# Radio_Unit.net
KiCad netlist of a schematic drawn in Altium Designer
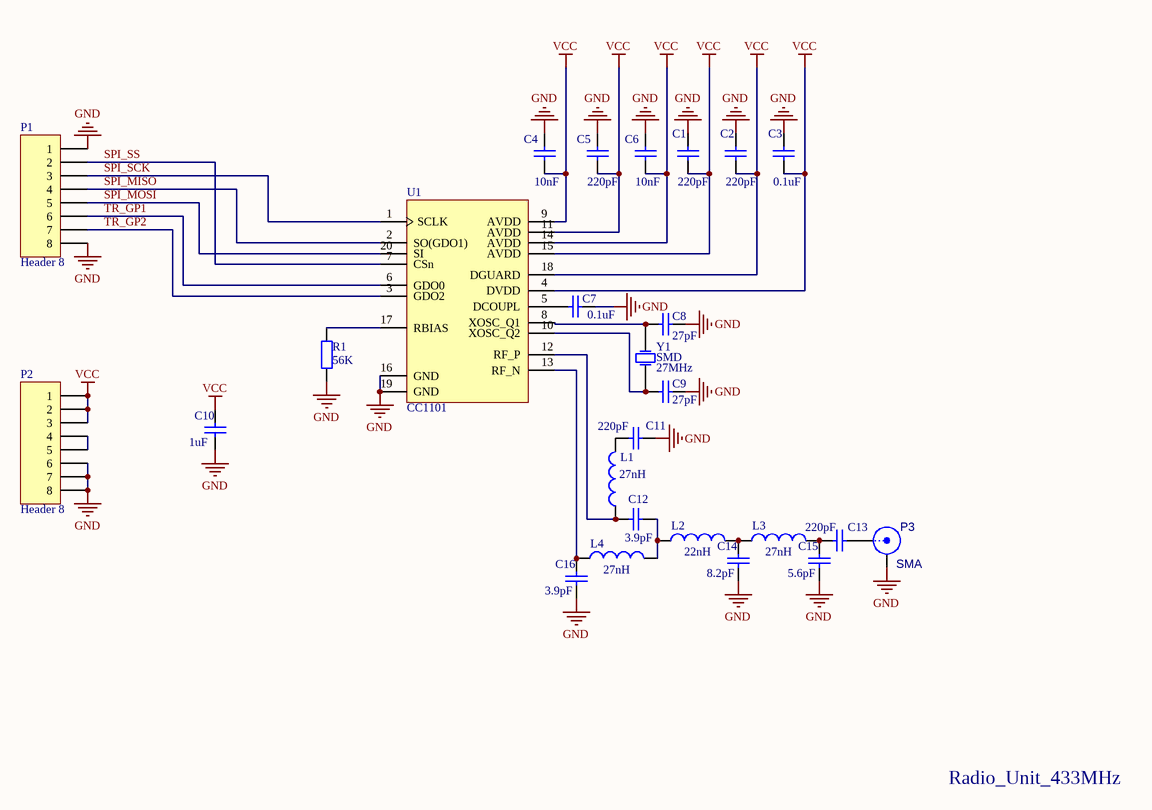
[diagram p0: Radio_Unit.SchDoc]

(export (version "E")
  (design (tool "Eeschema 10.0.6"))
  (components
    (comp (ref "C1")
      (value "220pF")
      (footprint "C0603")
      (description "Capasitor_SMD_0808/")
      (fields (field (name "Comment") "0805"))
      (libsource (lib "NEW") (part "Capasitor_SMD_0805"))
    )
    (comp (ref "C2")
      (value "220pF")
      (footprint "C0603")
      (description "Capasitor_SMD_0808/")
      (fields (field (name "Comment") "0805"))
      (libsource (lib "NEW") (part "Capasitor_SMD_0805"))
    )
    (comp (ref "C3")
      (value "0.1uF")
      (footprint "C0603")
      (description "Capasitor_SMD_0808/")
      (fields (field (name "Comment") "0805"))
      (libsource (lib "NEW") (part "Capasitor_SMD_0805"))
    )
    (comp (ref "C4")
      (value "10nF")
      (footprint "C0603")
      (description "Capasitor_SMD_0808/")
      (fields (field (name "Comment") "0805"))
      (libsource (lib "NEW") (part "Capasitor_SMD_0805"))
    )
    (comp (ref "C5")
      (value "220pF")
      (footprint "C0603")
      (description "Capasitor_SMD_0808/")
      (fields (field (name "Comment") "0805"))
      (libsource (lib "NEW") (part "Capasitor_SMD_0805"))
    )
    (comp (ref "C6")
      (value "10nF")
      (footprint "C0603")
      (description "Capasitor_SMD_0808/")
      (fields (field (name "Comment") "0805"))
      (libsource (lib "NEW") (part "Capasitor_SMD_0805"))
    )
    (comp (ref "C7")
      (value "0.1uF")
      (footprint "C0603")
      (description "Capasitor_SMD_0808/")
      (fields (field (name "Comment") "0805"))
      (libsource (lib "NEW") (part "Capasitor_SMD_0805"))
    )
    (comp (ref "C8")
      (value "27pF")
      (footprint "C0603")
      (description "Capasitor_SMD_0808/")
      (fields (field (name "Comment") "0805"))
      (libsource (lib "NEW") (part "Capasitor_SMD_0805"))
    )
    (comp (ref "C9")
      (value "27pF")
      (footprint "C0603")
      (description "Capasitor_SMD_0808/")
      (fields (field (name "Comment") "0805"))
      (libsource (lib "NEW") (part "Capasitor_SMD_0805"))
    )
    (comp (ref "C10")
      (value "1uF")
      (footprint "C0603")
      (description "Capasitor_SMD_0808/")
      (fields (field (name "Comment") "0805"))
      (libsource (lib "NEW") (part "Capasitor_SMD_0805"))
    )
    (comp (ref "C11")
      (value "220pF")
      (footprint "C0603")
      (description "Capasitor_SMD_0808/")
      (fields (field (name "Comment") "0805"))
      (libsource (lib "NEW") (part "Capasitor_SMD_0805"))
    )
    (comp (ref "C12")
      (value "3.9pF")
      (footprint "C0603")
      (description "Capasitor_SMD_0808/")
      (fields (field (name "Comment") "0805"))
      (libsource (lib "NEW") (part "Capasitor_SMD_0805"))
    )
    (comp (ref "C13")
      (value "220pF")
      (footprint "C0603")
      (description "Capasitor_SMD_0808/")
      (fields (field (name "Comment") "0805"))
      (libsource (lib "NEW") (part "Capasitor_SMD_0805"))
    )
    (comp (ref "C14")
      (value "8.2pF")
      (footprint "C0603")
      (description "Capasitor_SMD_0808/")
      (fields (field (name "Comment") "0805"))
      (libsource (lib "NEW") (part "Capasitor_SMD_0805"))
    )
    (comp (ref "C15")
      (value "5.6pF")
      (footprint "C0603")
      (description "Capasitor_SMD_0808/")
      (fields (field (name "Comment") "0805"))
      (libsource (lib "NEW") (part "Capasitor_SMD_0805"))
    )
    (comp (ref "C16")
      (value "3.9pF")
      (footprint "C0603")
      (description "Capasitor_SMD_0808/")
      (fields (field (name "Comment") "0805"))
      (libsource (lib "NEW") (part "Capasitor_SMD_0805"))
    )
    (comp (ref "L1")
      (value "27nH")
      (footprint "L0603")
      (fields (field (name "Comment") "SMD"))
      (libsource (lib "NEW") (part "Induktor_SMD"))
    )
    (comp (ref "L2")
      (value "22nH")
      (footprint "L0603")
      (fields (field (name "Comment") "SMD"))
      (libsource (lib "NEW") (part "Induktor_SMD"))
    )
    (comp (ref "L3")
      (value "27nH")
      (footprint "L0603")
      (fields (field (name "Comment") "SMD"))
      (libsource (lib "NEW") (part "Induktor_SMD"))
    )
    (comp (ref "L4")
      (value "27nH")
      (footprint "L0603")
      (fields (field (name "Comment") "SMD"))
      (libsource (lib "NEW") (part "Induktor_SMD"))
    )
    (comp (ref "P1")
      (value "Header 8")
      (footprint "HDR1X8")
      (description "Header, 8-Pin")
      (fields (field (name "PUBLISHER") "Altium Limited"))
      (libsource (lib "Miscellaneous Connectors") (part "Header 8"))
    )
    (comp (ref "P2")
      (value "Header 8")
      (footprint "HDR1X8")
      (description "Header, 8-Pin")
      (fields (field (name "PUBLISHER") "Altium Limited"))
      (libsource (lib "Miscellaneous Connectors") (part "Header 8"))
    )
    (comp (ref "P3")
      (value "SMA")
      (footprint "SMA")
      (fields (field (name "PUBLISHER") "Altium Limited"))
      (libsource (lib "NEW") (part "SMA"))
    )
    (comp (ref "R1")
      (value "56K")
      (footprint "C0603")
      (description "Resistor")
      (fields (field (name "Comment") "RES"))
      (libsource (lib "NEW") (part "RES"))
    )
    (comp (ref "U1") (value "CC1101") (footprint "VQFN20") (libsource (lib "NEW") (part "CC1101")))
    (comp (ref "Y1")
      (value "SMD")
      (footprint "Quartz_SMD0603")
      (fields (field (name "ALTIUM_UNNAMED_1") "27MHz"))
      (libsource (lib "NEW") (part "Quartz_SMD"))
    )
  )
  (nets
    (net (code "1") (name "/SPI_MISO") (class "Default")
      (node (ref "P1") (pin "4") (pinfunction "4_4") (pintype "passive"))
      (node (ref "U1") (pin "2") (pinfunction "SO(GDO1)_2") (pintype "passive"))
    )
    (net (code "2") (name "/SPI_MOSI") (class "Default")
      (node (ref "P1") (pin "5") (pinfunction "5_5") (pintype "passive"))
      (node (ref "U1") (pin "20") (pinfunction "SI_20") (pintype "passive"))
    )
    (net (code "3") (name "/SPI_SCK") (class "Default")
      (node (ref "P1") (pin "3") (pinfunction "3_3") (pintype "passive"))
      (node (ref "U1") (pin "1") (pinfunction "SCLK_1") (pintype "passive"))
    )
    (net (code "4") (name "/SPI_SS") (class "Default")
      (node (ref "P1") (pin "2") (pinfunction "2_2") (pintype "passive"))
      (node (ref "U1") (pin "7") (pinfunction "CSn_7") (pintype "passive"))
    )
    (net (code "5") (name "/TR_GP1") (class "Default")
      (node (ref "P1") (pin "6") (pinfunction "6_6") (pintype "passive"))
      (node (ref "U1") (pin "6") (pinfunction "GDO0_6") (pintype "passive"))
    )
    (net (code "6") (name "/TR_GP2") (class "Default")
      (node (ref "P1") (pin "7") (pinfunction "7_7") (pintype "passive"))
      (node (ref "U1") (pin "3") (pinfunction "GDO2_3") (pintype "passive"))
    )
    (net (code "7") (name "GND") (class "Default")
      (node (ref "C1") (pin "1") (pinfunction "1_1") (pintype "passive"))
      (node (ref "C10") (pin "2") (pinfunction "2_2") (pintype "passive"))
      (node (ref "C11") (pin "2") (pinfunction "2_2") (pintype "passive"))
      (node (ref "C14") (pin "1") (pinfunction "1_1") (pintype "passive"))
      (node (ref "C15") (pin "1") (pinfunction "1_1") (pintype "passive"))
      (node (ref "C16") (pin "1") (pinfunction "1_1") (pintype "passive"))
      (node (ref "C2") (pin "1") (pinfunction "1_1") (pintype "passive"))
      (node (ref "C3") (pin "1") (pinfunction "1_1") (pintype "passive"))
      (node (ref "C4") (pin "1") (pinfunction "1_1") (pintype "passive"))
      (node (ref "C5") (pin "1") (pinfunction "1_1") (pintype "passive"))
      (node (ref "C6") (pin "1") (pinfunction "1_1") (pintype "passive"))
      (node (ref "C7") (pin "2") (pinfunction "2_2") (pintype "passive"))
      (node (ref "C8") (pin "2") (pinfunction "2_2") (pintype "passive"))
      (node (ref "C9") (pin "2") (pinfunction "2_2") (pintype "passive"))
      (node (ref "P1") (pin "1") (pinfunction "1_1") (pintype "passive"))
      (node (ref "P1") (pin "8") (pinfunction "8_8") (pintype "passive"))
      (node (ref "P2") (pin "6") (pinfunction "6_6") (pintype "passive"))
      (node (ref "P2") (pin "7") (pinfunction "7_7") (pintype "passive"))
      (node (ref "P2") (pin "8") (pinfunction "8_8") (pintype "passive"))
      (node (ref "P3") (pin "2") (pinfunction "Y_2") (pintype "passive"))
      (node (ref "R1") (pin "1") (pinfunction "1_1") (pintype "passive"))
      (node (ref "U1") (pin "16") (pinfunction "GND_16") (pintype "passive"))
      (node (ref "U1") (pin "19") (pinfunction "GND_19") (pintype "passive"))
    )
    (net (code "8") (name "Net-(C11-Pad1)") (class "Default")
      (node (ref "C11") (pin "1") (pinfunction "1_1") (pintype "passive"))
      (node (ref "L1") (pin "2") (pinfunction "2_2") (pintype "passive"))
    )
    (net (code "9") (name "Net-(C12-Pad1)") (class "Default")
      (node (ref "C12") (pin "1") (pinfunction "1_1") (pintype "passive"))
      (node (ref "L2") (pin "1") (pinfunction "1_1") (pintype "passive"))
      (node (ref "L4") (pin "2") (pinfunction "2_2") (pintype "passive"))
    )
    (net (code "10") (name "Net-(C13-Pad1)") (class "Default")
      (node (ref "C13") (pin "1") (pinfunction "1_1") (pintype "passive"))
      (node (ref "C15") (pin "2") (pinfunction "2_2") (pintype "passive"))
      (node (ref "L3") (pin "2") (pinfunction "2_2") (pintype "passive"))
    )
    (net (code "11") (name "Net-(C14-Pad2)") (class "Default")
      (node (ref "C14") (pin "2") (pinfunction "2_2") (pintype "passive"))
      (node (ref "L2") (pin "2") (pinfunction "2_2") (pintype "passive"))
      (node (ref "L3") (pin "1") (pinfunction "1_1") (pintype "passive"))
    )
    (net (code "12") (name "Net-(P2-Pad4)") (class "Default")
      (node (ref "P2") (pin "4") (pinfunction "4_4") (pintype "passive"))
      (node (ref "P2") (pin "5") (pinfunction "5_5") (pintype "passive"))
    )
    (net (code "13") (name "Net-(P3-X)") (class "Default")
      (node (ref "C13") (pin "2") (pinfunction "2_2") (pintype "passive"))
      (node (ref "P3") (pin "1") (pinfunction "X_1") (pintype "passive"))
    )
    (net (code "14") (name "Net-(U1-DCOUPL)") (class "Default")
      (node (ref "C7") (pin "1") (pinfunction "1_1") (pintype "passive"))
      (node (ref "U1") (pin "5") (pinfunction "DCOUPL_5") (pintype "passive"))
    )
    (net (code "15") (name "Net-(U1-RBIAS)") (class "Default")
      (node (ref "R1") (pin "2") (pinfunction "2_2") (pintype "passive"))
      (node (ref "U1") (pin "17") (pinfunction "RBIAS_17") (pintype "passive"))
    )
    (net (code "16") (name "Net-(U1-RF_N)") (class "Default")
      (node (ref "C16") (pin "2") (pinfunction "2_2") (pintype "passive"))
      (node (ref "L4") (pin "1") (pinfunction "1_1") (pintype "passive"))
      (node (ref "U1") (pin "13") (pinfunction "RF_N_13") (pintype "passive"))
    )
    (net (code "17") (name "Net-(U1-RF_P)") (class "Default")
      (node (ref "C12") (pin "2") (pinfunction "2_2") (pintype "passive"))
      (node (ref "L1") (pin "1") (pinfunction "1_1") (pintype "passive"))
      (node (ref "U1") (pin "12") (pinfunction "RF_P_12") (pintype "passive"))
    )
    (net (code "18") (name "Net-(U1-XOSC_Q1)") (class "Default")
      (node (ref "C8") (pin "1") (pinfunction "1_1") (pintype "passive"))
      (node (ref "U1") (pin "8") (pinfunction "XOSC_Q1_8") (pintype "passive"))
      (node (ref "Y1") (pin "1") (pinfunction "OSC1_1") (pintype "passive"))
    )
    (net (code "19") (name "Net-(U1-XOSC_Q2)") (class "Default")
      (node (ref "C9") (pin "1") (pinfunction "1_1") (pintype "passive"))
      (node (ref "U1") (pin "10") (pinfunction "XOSC_Q2_10") (pintype "passive"))
      (node (ref "Y1") (pin "3") (pinfunction "OSC2_3") (pintype "passive"))
    )
    (net (code "20") (name "VCC") (class "Default")
      (node (ref "C1") (pin "2") (pinfunction "2_2") (pintype "passive"))
      (node (ref "C10") (pin "1") (pinfunction "1_1") (pintype "passive"))
      (node (ref "C2") (pin "2") (pinfunction "2_2") (pintype "passive"))
      (node (ref "C3") (pin "2") (pinfunction "2_2") (pintype "passive"))
      (node (ref "C4") (pin "2") (pinfunction "2_2") (pintype "passive"))
      (node (ref "C5") (pin "2") (pinfunction "2_2") (pintype "passive"))
      (node (ref "C6") (pin "2") (pinfunction "2_2") (pintype "passive"))
      (node (ref "P2") (pin "1") (pinfunction "1_1") (pintype "passive"))
      (node (ref "P2") (pin "2") (pinfunction "2_2") (pintype "passive"))
      (node (ref "P2") (pin "3") (pinfunction "3_3") (pintype "passive"))
      (node (ref "U1") (pin "11") (pinfunction "AVDD_11") (pintype "passive"))
      (node (ref "U1") (pin "14") (pinfunction "AVDD_14") (pintype "passive"))
      (node (ref "U1") (pin "15") (pinfunction "AVDD_15") (pintype "passive"))
      (node (ref "U1") (pin "18") (pinfunction "DGUARD_18") (pintype "passive"))
      (node (ref "U1") (pin "4") (pinfunction "DVDD_4") (pintype "passive"))
      (node (ref "U1") (pin "9") (pinfunction "AVDD_9") (pintype "passive"))
    )
  )
)
